# 06-SD_CARD.net
KiCad netlist of a schematic drawn in Altium Designer
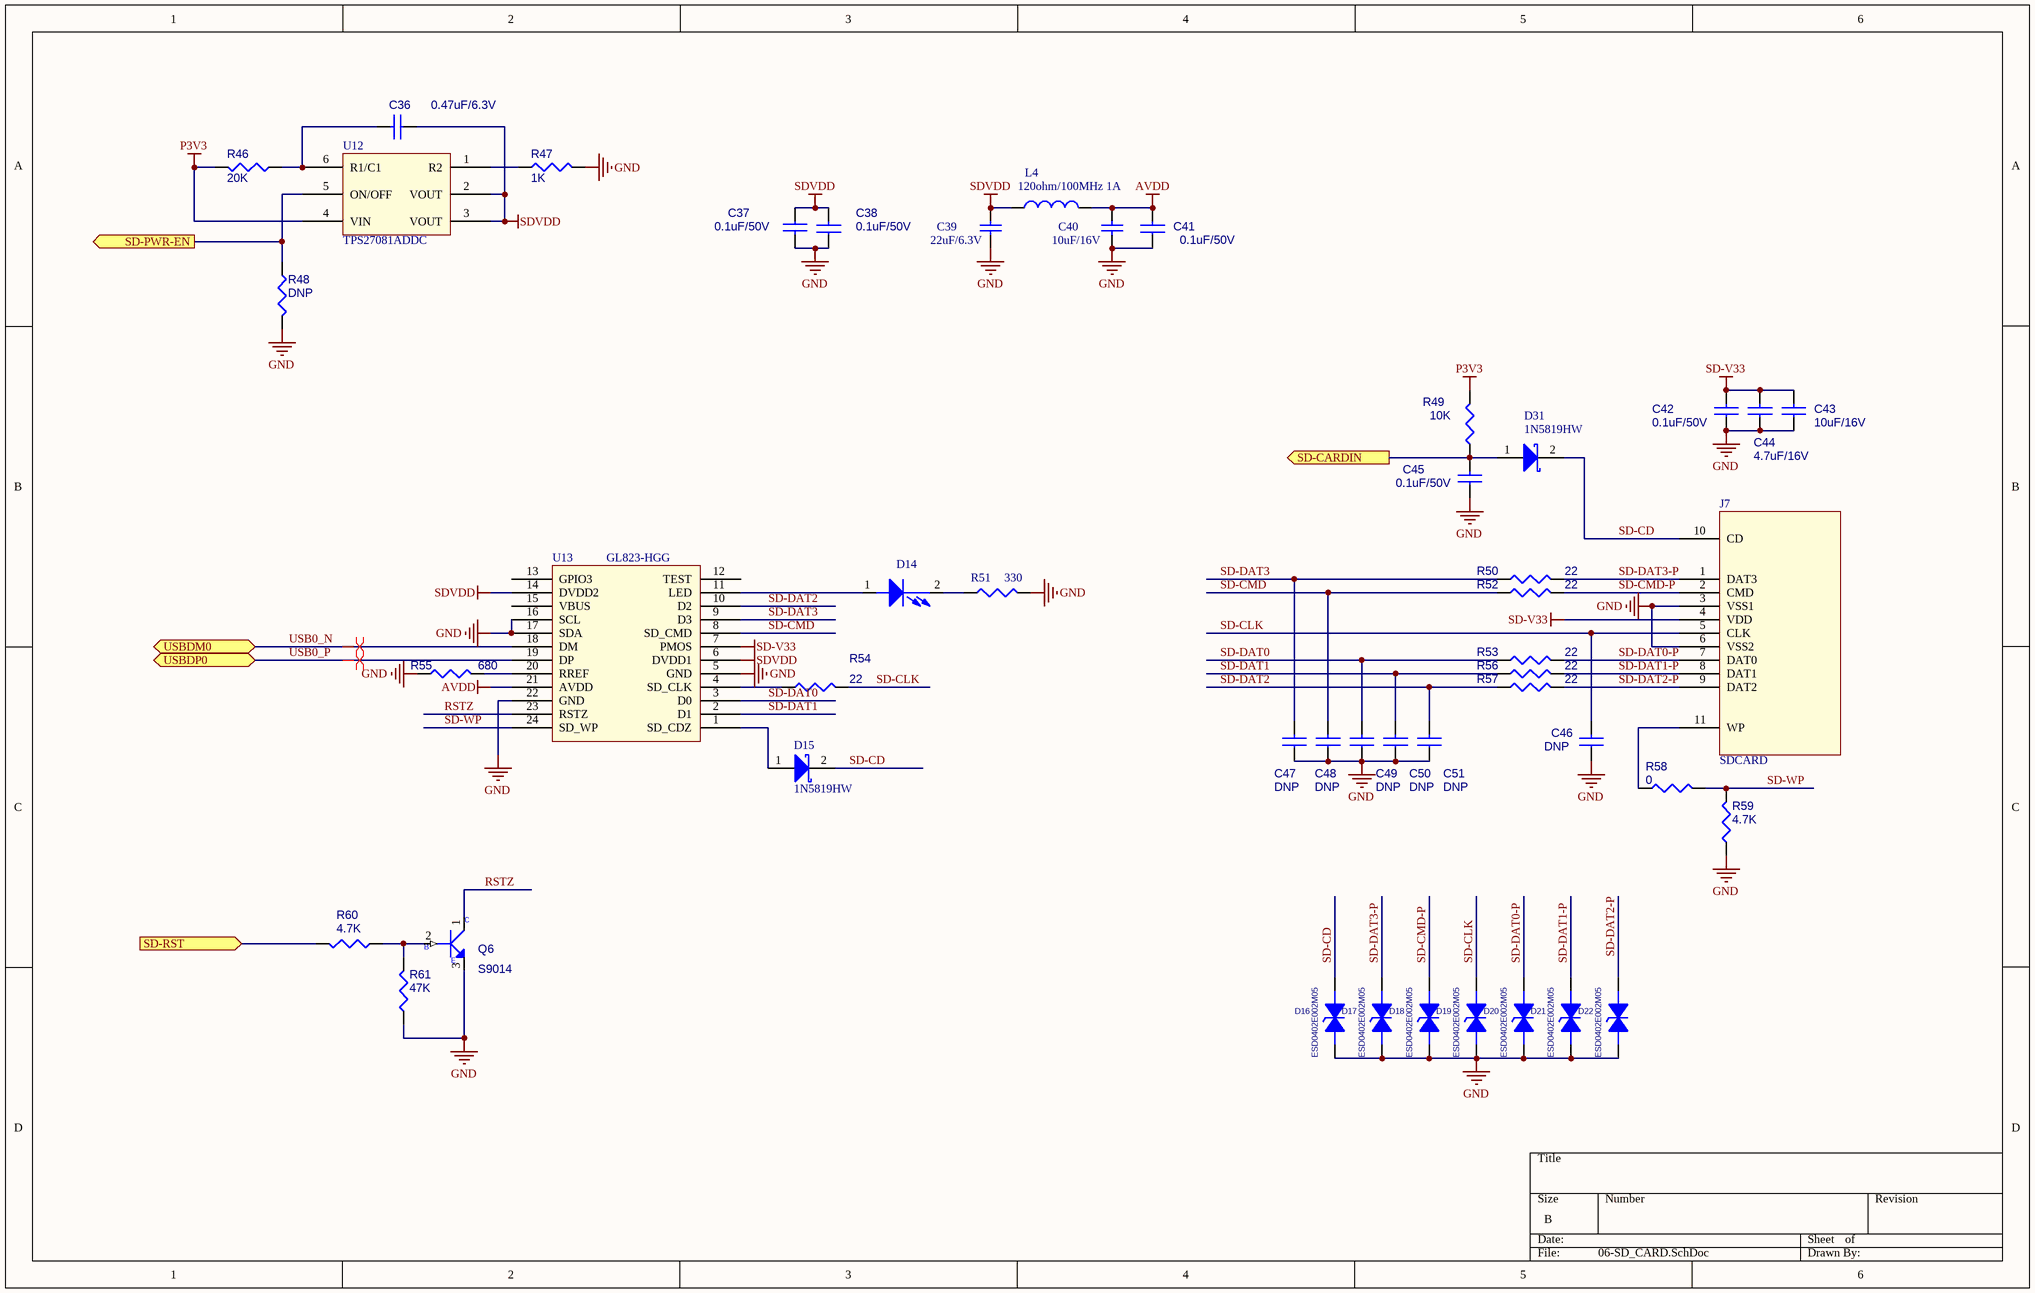
[diagram p0: 06-SD_CARD.SchDoc]

(export (version "E")
  (design (tool "Eeschema 10.0.6"))
  (components
    (comp (ref "C36") (value "0.47uF/6.3V") (footprint "0402") (libsource (lib "*") (part "P_CAP NP")))
    (comp (ref "C37") (value "0.1uF/50V") (libsource (lib "*") (part "CAP")))
    (comp (ref "C38") (value "0.1uF/50V") (libsource (lib "*") (part "CAP")))
    (comp (ref "C39")
      (value "22uF/6.3V")
      (footprint "0805")
      (description "Capacitor")
      (fields (field (name "PUBLISHER") "Altium Limited"))
      (libsource (lib "Miscellaneous Devices") (part "Cap"))
    )
    (comp (ref "C40")
      (value "10uF/16V")
      (footprint "0805")
      (description "Capacitor")
      (fields (field (name "PUBLISHER") "Altium Limited"))
      (libsource (lib "Miscellaneous Devices") (part "Cap"))
    )
    (comp (ref "C41") (value "0.1uF/50V") (libsource (lib "*") (part "CAP")))
    (comp (ref "C42") (value "0.1uF/50V") (libsource (lib "*") (part "CAP")))
    (comp (ref "C43") (value "10uF/16V") (libsource (lib "*") (part "CAP")))
    (comp (ref "C44") (value "4.7uF/16V") (libsource (lib "*") (part "CAP")))
    (comp (ref "C45") (value "0.1uF/50V") (libsource (lib "*") (part "CAP")))
    (comp (ref "C46") (value "DNP") (libsource (lib "*") (part "CAP")))
    (comp (ref "C47") (value "DNP") (libsource (lib "*") (part "CAP")))
    (comp (ref "C48") (value "DNP") (libsource (lib "*") (part "CAP")))
    (comp (ref "C49") (value "DNP") (libsource (lib "*") (part "CAP")))
    (comp (ref "C50") (value "DNP") (libsource (lib "*") (part "CAP")))
    (comp (ref "C51") (value "DNP") (libsource (lib "*") (part "CAP")))
    (comp (ref "D14") (value "LED GREEN") (footprint "LED0603") (libsource (lib "*") (part "LN01401_1")))
    (comp (ref "D15")
      (value "1N5819HW")
      (footprint "1N5819")
      (description "Schottky Rectifier")
      (libsource (lib "Miscellaneous Devices") (part "Diode 11DQ03"))
    )
    (comp (ref "D16") (value "ESD0402E002M05") (libsource (lib "*") (part "PESD")))
    (comp (ref "D17") (value "ESD0402E002M05") (libsource (lib "*") (part "PESD")))
    (comp (ref "D18") (value "ESD0402E002M05") (libsource (lib "*") (part "PESD")))
    (comp (ref "D19") (value "ESD0402E002M05") (libsource (lib "*") (part "PESD")))
    (comp (ref "D20") (value "ESD0402E002M05") (libsource (lib "*") (part "PESD")))
    (comp (ref "D21") (value "ESD0402E002M05") (libsource (lib "*") (part "PESD")))
    (comp (ref "D22") (value "ESD0402E002M05") (libsource (lib "*") (part "PESD")))
    (comp (ref "D31")
      (value "1N5819HW")
      (footprint "1N5819")
      (description "Schottky Rectifier")
      (libsource (lib "Miscellaneous Devices") (part "Diode 11DQ03"))
    )
    (comp (ref "J7") (value "SDCARD") (footprint "SDCARD") (libsource (lib "Schlib") (part "SDCARD")))
    (comp (ref "L4")
      (value "120ohm/100MHz 1A")
      (footprint "0603")
      (description "Inductor")
      (fields (field (name "PUBLISHER") "Altium Limited"))
      (libsource (lib "Miscellaneous Devices") (part "Inductor"))
    )
    (comp (ref "Q6")
      (value "S9014")
      (footprint "NPN")
      (fields (field (name "PART NUMBER") "SB039040000"))
      (libsource (lib "*") (part "MMBT3904_NL_SOT23-3"))
    )
    (comp (ref "R46") (value "20K") (footprint "0402") (libsource (lib "*") (part "P_R")))
    (comp (ref "R47") (value "1K") (footprint "0402") (libsource (lib "*") (part "P_R")))
    (comp (ref "R48") (value "DNP") (footprint "0402") (libsource (lib "*") (part "P_R")))
    (comp (ref "R49") (value "10K") (footprint "0402") (libsource (lib "*") (part "P_R")))
    (comp (ref "R50") (value "22") (footprint "0402") (libsource (lib "*") (part "P_R")))
    (comp (ref "R51") (value "330") (footprint "0402") (libsource (lib "*") (part "CR16-1003FM")))
    (comp (ref "R52") (value "22") (footprint "0402") (libsource (lib "*") (part "P_R")))
    (comp (ref "R53") (value "22") (footprint "0402") (libsource (lib "*") (part "P_R")))
    (comp (ref "R54") (value "22") (footprint "0402") (libsource (lib "*") (part "P_R")))
    (comp (ref "R55") (value "680") (footprint "0402") (libsource (lib "*") (part "P_R")))
    (comp (ref "R56") (value "22") (footprint "0402") (libsource (lib "*") (part "P_R")))
    (comp (ref "R57") (value "22") (footprint "0402") (libsource (lib "*") (part "P_R")))
    (comp (ref "R58") (value "0") (footprint "0402") (libsource (lib "*") (part "P_R")))
    (comp (ref "R59") (value "4.7K") (footprint "0402") (libsource (lib "*") (part "P_R")))
    (comp (ref "R60") (value "4.7K") (footprint "0402") (libsource (lib "*") (part "P_R")))
    (comp (ref "R61") (value "47K") (footprint "0402") (libsource (lib "*") (part "P_R")))
    (comp (ref "U12")
      (value "TPS27081ADDC")
      (footprint "SOT23-6")
      (libsource (lib "Schlib") (part "TPS27081A"))
    )
    (comp (ref "U13") (value "GL823-HGG") (footprint "SSOP24") (libsource (lib "Schlib") (part "GL823")))
  )
  (nets
    (net (code "1") (name "/RSTZ") (class "Default")
      (node (ref "Q6") (pin "1") (pinfunction "COLLECTOR_1") (pintype "passive"))
      (node (ref "U13") (pin "23") (pinfunction "RSTZ_23") (pintype "passive"))
    )
    (net (code "2") (name "/SD-CARDIN") (class "Default")
      (node (ref "C45") (pin "2") (pinfunction "2_2") (pintype "passive"))
      (node (ref "D31") (pin "1") (pinfunction "A_1") (pintype "passive"))
      (node (ref "R49") (pin "2") (pinfunction "2_2") (pintype "passive"))
    )
    (net (code "3") (name "/SD-CD") (class "Default")
      (node (ref "D15") (pin "2") (pinfunction "K_2") (pintype "passive"))
      (node (ref "D16") (pin "2") (pinfunction "2_2") (pintype "passive"))
      (node (ref "D31") (pin "2") (pinfunction "K_2") (pintype "passive"))
      (node (ref "J7") (pin "10") (pinfunction "CD_10") (pintype "passive"))
    )
    (net (code "4") (name "/SD-CLK") (class "Default")
      (node (ref "C46") (pin "2") (pinfunction "2_2") (pintype "passive"))
      (node (ref "D19") (pin "2") (pinfunction "2_2") (pintype "passive"))
      (node (ref "J7") (pin "5") (pinfunction "CLK_5") (pintype "passive"))
      (node (ref "R54") (pin "1") (pinfunction "1_1") (pintype "passive"))
    )
    (net (code "5") (name "/SD-CMD") (class "Default")
      (node (ref "C48") (pin "2") (pinfunction "2_2") (pintype "passive"))
      (node (ref "R52") (pin "2") (pinfunction "2_2") (pintype "passive"))
      (node (ref "U13") (pin "8") (pinfunction "SD_CMD_8") (pintype "passive"))
    )
    (net (code "6") (name "/SD-CMD-P") (class "Default")
      (node (ref "D18") (pin "2") (pinfunction "2_2") (pintype "passive"))
      (node (ref "J7") (pin "2") (pinfunction "CMD_2") (pintype "passive"))
      (node (ref "R52") (pin "1") (pinfunction "1_1") (pintype "passive"))
    )
    (net (code "7") (name "/SD-DAT0") (class "Default")
      (node (ref "C49") (pin "2") (pinfunction "2_2") (pintype "passive"))
      (node (ref "R53") (pin "2") (pinfunction "2_2") (pintype "passive"))
      (node (ref "U13") (pin "3") (pinfunction "D0_3") (pintype "passive"))
    )
    (net (code "8") (name "/SD-DAT0-P") (class "Default")
      (node (ref "D20") (pin "2") (pinfunction "2_2") (pintype "passive"))
      (node (ref "J7") (pin "7") (pinfunction "DAT0_7") (pintype "passive"))
      (node (ref "R53") (pin "1") (pinfunction "1_1") (pintype "passive"))
    )
    (net (code "9") (name "/SD-DAT1") (class "Default")
      (node (ref "C50") (pin "2") (pinfunction "2_2") (pintype "passive"))
      (node (ref "R56") (pin "2") (pinfunction "2_2") (pintype "passive"))
      (node (ref "U13") (pin "2") (pinfunction "D1_2") (pintype "passive"))
    )
    (net (code "10") (name "/SD-DAT1-P") (class "Default")
      (node (ref "D21") (pin "2") (pinfunction "2_2") (pintype "passive"))
      (node (ref "J7") (pin "8") (pinfunction "DAT1_8") (pintype "passive"))
      (node (ref "R56") (pin "1") (pinfunction "1_1") (pintype "passive"))
    )
    (net (code "11") (name "/SD-DAT2") (class "Default")
      (node (ref "C51") (pin "2") (pinfunction "2_2") (pintype "passive"))
      (node (ref "R57") (pin "2") (pinfunction "2_2") (pintype "passive"))
      (node (ref "U13") (pin "10") (pinfunction "D2_10") (pintype "passive"))
    )
    (net (code "12") (name "/SD-DAT2-P") (class "Default")
      (node (ref "D22") (pin "2") (pinfunction "2_2") (pintype "passive"))
      (node (ref "J7") (pin "9") (pinfunction "DAT2_9") (pintype "passive"))
      (node (ref "R57") (pin "1") (pinfunction "1_1") (pintype "passive"))
    )
    (net (code "13") (name "/SD-DAT3") (class "Default")
      (node (ref "C47") (pin "2") (pinfunction "2_2") (pintype "passive"))
      (node (ref "R50") (pin "2") (pinfunction "2_2") (pintype "passive"))
      (node (ref "U13") (pin "9") (pinfunction "D3_9") (pintype "passive"))
    )
    (net (code "14") (name "/SD-DAT3-P") (class "Default")
      (node (ref "D17") (pin "2") (pinfunction "2_2") (pintype "passive"))
      (node (ref "J7") (pin "1") (pinfunction "DAT3_1") (pintype "passive"))
      (node (ref "R50") (pin "1") (pinfunction "1_1") (pintype "passive"))
    )
    (net (code "15") (name "/SD-PWR-EN") (class "Default")
      (node (ref "R48") (pin "2") (pinfunction "2_2") (pintype "passive"))
      (node (ref "U12") (pin "5") (pinfunction "ON/OFF_5") (pintype "passive"))
    )
    (net (code "16") (name "/SD-RST") (class "Default")
      (node (ref "R60") (pin "1") (pinfunction "1_1") (pintype "passive"))
    )
    (net (code "17") (name "/SD-WP") (class "Default")
      (node (ref "R58") (pin "1") (pinfunction "1_1") (pintype "passive"))
      (node (ref "R59") (pin "1") (pinfunction "1_1") (pintype "passive"))
      (node (ref "U13") (pin "24") (pinfunction "SD_WP_24") (pintype "passive"))
    )
    (net (code "18") (name "/USB0_N") (class "Default")
      (node (ref "U13") (pin "18") (pinfunction "DM_18") (pintype "passive"))
    )
    (net (code "19") (name "/USB0_P") (class "Default")
      (node (ref "U13") (pin "19") (pinfunction "DP_19") (pintype "passive"))
    )
    (net (code "20") (name "AVDD") (class "Default")
      (node (ref "C40") (pin "1") (pinfunction "1_1") (pintype "passive"))
      (node (ref "C41") (pin "2") (pinfunction "2_2") (pintype "passive"))
      (node (ref "L4") (pin "2") (pinfunction "2_2") (pintype "passive"))
      (node (ref "U13") (pin "21") (pinfunction "AVDD_21") (pintype "passive"))
    )
    (net (code "21") (name "GND") (class "Default")
      (node (ref "C37") (pin "2") (pinfunction "2_2") (pintype "passive"))
      (node (ref "C38") (pin "1") (pinfunction "1_1") (pintype "passive"))
      (node (ref "C39") (pin "2") (pinfunction "2_2") (pintype "passive"))
      (node (ref "C40") (pin "2") (pinfunction "2_2") (pintype "passive"))
      (node (ref "C41") (pin "1") (pinfunction "1_1") (pintype "passive"))
      (node (ref "C42") (pin "1") (pinfunction "1_1") (pintype "passive"))
      (node (ref "C43") (pin "1") (pinfunction "1_1") (pintype "passive"))
      (node (ref "C44") (pin "1") (pinfunction "1_1") (pintype "passive"))
      (node (ref "C45") (pin "1") (pinfunction "1_1") (pintype "passive"))
      (node (ref "C46") (pin "1") (pinfunction "1_1") (pintype "passive"))
      (node (ref "C47") (pin "1") (pinfunction "1_1") (pintype "passive"))
      (node (ref "C48") (pin "1") (pinfunction "1_1") (pintype "passive"))
      (node (ref "C49") (pin "1") (pinfunction "1_1") (pintype "passive"))
      (node (ref "C50") (pin "1") (pinfunction "1_1") (pintype "passive"))
      (node (ref "C51") (pin "1") (pinfunction "1_1") (pintype "passive"))
      (node (ref "D16") (pin "1") (pinfunction "1_1") (pintype "passive"))
      (node (ref "D17") (pin "1") (pinfunction "1_1") (pintype "passive"))
      (node (ref "D18") (pin "1") (pinfunction "1_1") (pintype "passive"))
      (node (ref "D19") (pin "1") (pinfunction "1_1") (pintype "passive"))
      (node (ref "D20") (pin "1") (pinfunction "1_1") (pintype "passive"))
      (node (ref "D21") (pin "1") (pinfunction "1_1") (pintype "passive"))
      (node (ref "D22") (pin "1") (pinfunction "1_1") (pintype "passive"))
      (node (ref "J7") (pin "3") (pinfunction "VSS1_3") (pintype "passive"))
      (node (ref "J7") (pin "6") (pinfunction "VSS2_6") (pintype "passive"))
      (node (ref "Q6") (pin "3") (pinfunction "EMITTER_3") (pintype "passive"))
      (node (ref "R47") (pin "1") (pinfunction "1_1") (pintype "passive"))
      (node (ref "R48") (pin "1") (pinfunction "1_1") (pintype "passive"))
      (node (ref "R51") (pin "1") (pinfunction "1_1") (pintype "passive"))
      (node (ref "R55") (pin "2") (pinfunction "2_2") (pintype "passive"))
      (node (ref "R59") (pin "2") (pinfunction "2_2") (pintype "passive"))
      (node (ref "R61") (pin "2") (pinfunction "2_2") (pintype "passive"))
      (node (ref "U13") (pin "16") (pinfunction "SCL_16") (pintype "passive"))
      (node (ref "U13") (pin "17") (pinfunction "SDA_17") (pintype "passive"))
      (node (ref "U13") (pin "22") (pinfunction "GND_22") (pintype "passive"))
      (node (ref "U13") (pin "5") (pinfunction "GND_5") (pintype "passive"))
    )
    (net (code "22") (name "Net-(D14-ANODE)") (class "Default")
      (node (ref "D14") (pin "1") (pinfunction "ANODE_1") (pintype "passive"))
      (node (ref "U13") (pin "11") (pinfunction "LED_11") (pintype "passive"))
    )
    (net (code "23") (name "Net-(D14-CATHODE)") (class "Default")
      (node (ref "D14") (pin "2") (pinfunction "CATHODE_2") (pintype "passive"))
      (node (ref "R51") (pin "2") (pinfunction "2_2") (pintype "passive"))
    )
    (net (code "24") (name "Net-(D15-A)") (class "Default")
      (node (ref "D15") (pin "1") (pinfunction "A_1") (pintype "passive"))
      (node (ref "U13") (pin "1") (pinfunction "SD_CDZ_1") (pintype "passive"))
    )
    (net (code "25") (name "Net-(J7-WP)") (class "Default")
      (node (ref "J7") (pin "11") (pinfunction "WP_11") (pintype "passive"))
      (node (ref "R58") (pin "2") (pinfunction "2_2") (pintype "passive"))
    )
    (net (code "26") (name "Net-(Q6-BASE)") (class "Default")
      (node (ref "Q6") (pin "2") (pinfunction "BASE_2") (pintype "input"))
      (node (ref "R60") (pin "2") (pinfunction "2_2") (pintype "passive"))
      (node (ref "R61") (pin "1") (pinfunction "1_1") (pintype "passive"))
    )
    (net (code "27") (name "Net-(U12-R1{slash}C1)") (class "Default")
      (node (ref "C36") (pin "2") (pinfunction "2_2") (pintype "passive"))
      (node (ref "R46") (pin "2") (pinfunction "2_2") (pintype "passive"))
      (node (ref "U12") (pin "6") (pinfunction "R1/C1_6") (pintype "passive"))
    )
    (net (code "28") (name "Net-(U12-R2)") (class "Default")
      (node (ref "R47") (pin "2") (pinfunction "2_2") (pintype "passive"))
      (node (ref "U12") (pin "1") (pinfunction "R2_1") (pintype "passive"))
    )
    (net (code "29") (name "Net-(U13-RREF)") (class "Default")
      (node (ref "R55") (pin "1") (pinfunction "1_1") (pintype "passive"))
      (node (ref "U13") (pin "20") (pinfunction "RREF_20") (pintype "passive"))
    )
    (net (code "30") (name "Net-(U13-SD_CLK)") (class "Default")
      (node (ref "R54") (pin "2") (pinfunction "2_2") (pintype "passive"))
      (node (ref "U13") (pin "4") (pinfunction "SD_CLK_4") (pintype "passive"))
    )
    (net (code "31") (name "P3V3") (class "Default")
      (node (ref "R46") (pin "1") (pinfunction "1_1") (pintype "passive"))
      (node (ref "R49") (pin "1") (pinfunction "1_1") (pintype "passive"))
      (node (ref "U12") (pin "4") (pinfunction "VIN_4") (pintype "passive"))
    )
    (net (code "32") (name "SD-V33") (class "Default")
      (node (ref "C42") (pin "2") (pinfunction "2_2") (pintype "passive"))
      (node (ref "C43") (pin "2") (pinfunction "2_2") (pintype "passive"))
      (node (ref "C44") (pin "2") (pinfunction "2_2") (pintype "passive"))
      (node (ref "J7") (pin "4") (pinfunction "VDD_4") (pintype "passive"))
      (node (ref "U13") (pin "7") (pinfunction "PMOS_7") (pintype "passive"))
    )
    (net (code "33") (name "SDVDD") (class "Default")
      (node (ref "C36") (pin "1") (pinfunction "1_1") (pintype "passive"))
      (node (ref "C37") (pin "1") (pinfunction "1_1") (pintype "passive"))
      (node (ref "C38") (pin "2") (pinfunction "2_2") (pintype "passive"))
      (node (ref "C39") (pin "1") (pinfunction "1_1") (pintype "passive"))
      (node (ref "L4") (pin "1") (pinfunction "1_1") (pintype "passive"))
      (node (ref "U12") (pin "2") (pinfunction "VOUT_2") (pintype "passive"))
      (node (ref "U12") (pin "3") (pinfunction "VOUT_3") (pintype "passive"))
      (node (ref "U13") (pin "14") (pinfunction "DVDD2_14") (pintype "passive"))
      (node (ref "U13") (pin "6") (pinfunction "DVDD1_6") (pintype "passive"))
    )
    (net (code "34") (name "unconnected-(U13-GPIO3-Pad13)") (class "Default")
      (node (ref "U13") (pin "13") (pinfunction "GPIO3_13") (pintype "passive"))
    )
    (net (code "35") (name "unconnected-(U13-TEST-Pad12)") (class "Default")
      (node (ref "U13") (pin "12") (pinfunction "TEST_12") (pintype "passive"))
    )
    (net (code "36") (name "unconnected-(U13-VBUS-Pad15)") (class "Default")
      (node (ref "U13") (pin "15") (pinfunction "VBUS_15") (pintype "passive"))
    )
  )
)
